# umodular_mega_shield_rev02.net
KiCad netlist of a schematic drawn in EAGLE
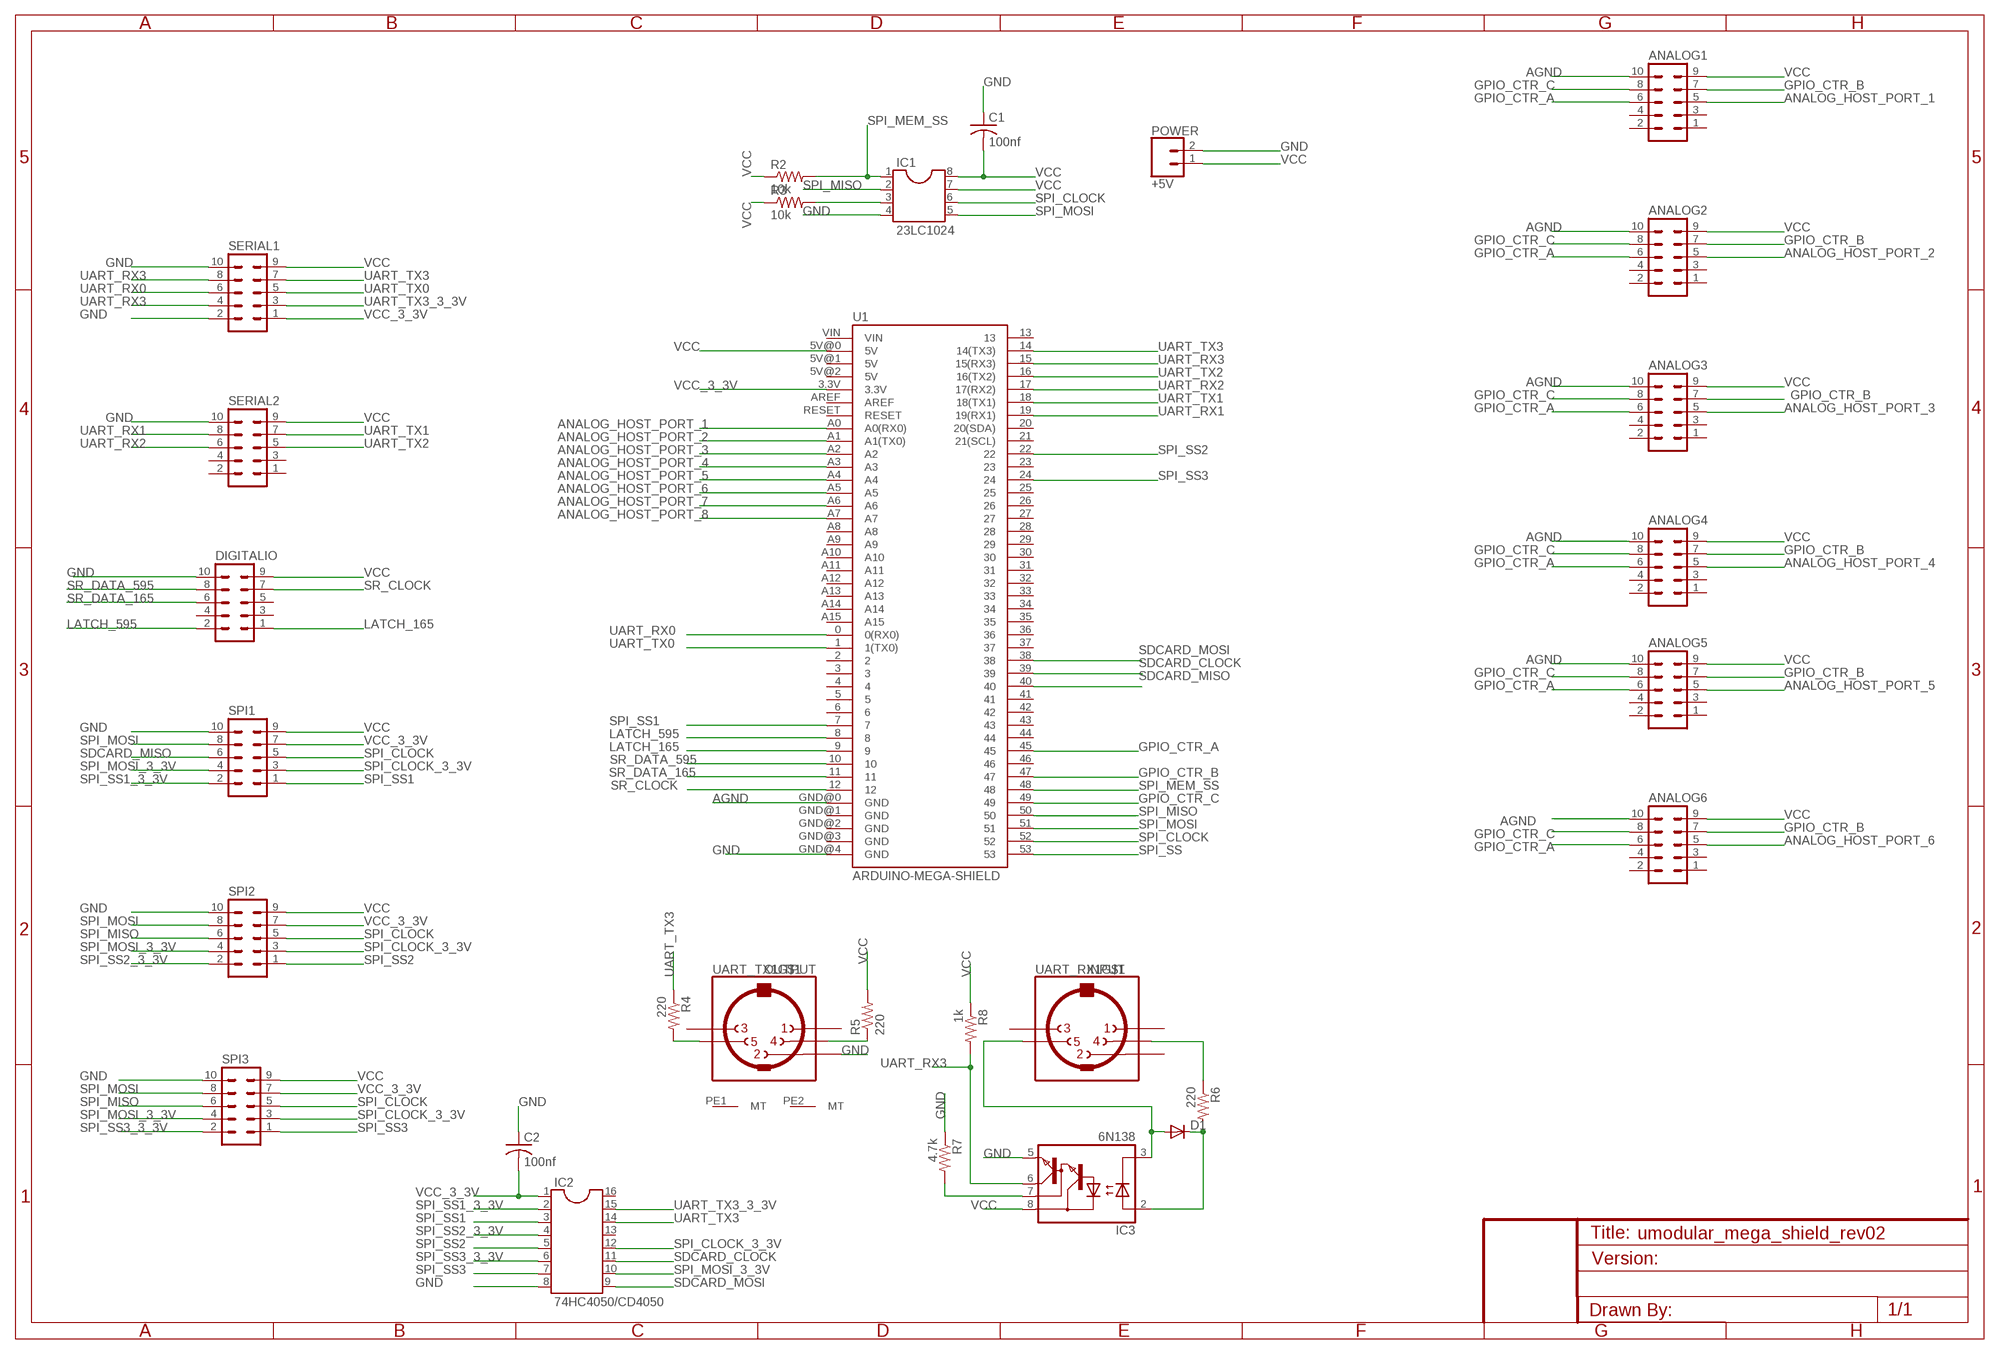
[diagram p0: schematic, sheet 1]

(export (version "E")
  (design (tool "Eeschema 10.0.6"))
  (components
    (comp (ref "ANALOG1")
      (value "MA05-2")
      (footprint "eagle-import:MA05-2")
      (libsource (lib "eagle-import") (part "MA05-2"))
    )
    (comp (ref "ANALOG2")
      (value "MA05-2")
      (footprint "eagle-import:MA05-2")
      (libsource (lib "eagle-import") (part "MA05-2"))
    )
    (comp (ref "ANALOG3")
      (value "MA05-2")
      (footprint "eagle-import:MA05-2")
      (libsource (lib "eagle-import") (part "MA05-2"))
    )
    (comp (ref "ANALOG4")
      (value "MA05-2")
      (footprint "eagle-import:MA05-2")
      (libsource (lib "eagle-import") (part "MA05-2"))
    )
    (comp (ref "ANALOG5")
      (value "MA05-2")
      (footprint "eagle-import:MA05-2")
      (libsource (lib "eagle-import") (part "MA05-2"))
    )
    (comp (ref "ANALOG6")
      (value "MA05-2")
      (footprint "eagle-import:MA05-2")
      (libsource (lib "eagle-import") (part "MA05-2"))
    )
    (comp (ref "C1")
      (value "100nf")
      (footprint "eagle-import:C050-024X044")
      (libsource (lib "eagle-import") (part "C-US050-024X044"))
    )
    (comp (ref "C2")
      (value "100nf")
      (footprint "eagle-import:C050-024X044")
      (libsource (lib "eagle-import") (part "C-US050-024X044"))
    )
    (comp (ref "D1")
      (value "1N4148DO35-7")
      (footprint "eagle-import:DO35-7")
      (libsource (lib "eagle-import") (part "1N4148DO35-7"))
    )
    (comp (ref "DIGITALIO")
      (value "MA05-2")
      (footprint "eagle-import:MA05-2")
      (libsource (lib "eagle-import") (part "MA05-2"))
    )
    (comp (ref "IC1")
      (value "23LC1024")
      (footprint "eagle-import:DIL08")
      (libsource (lib "eagle-import") (part "DIL8"))
    )
    (comp (ref "IC2")
      (value "74HC4050/CD4050")
      (footprint "eagle-import:DIL16")
      (libsource (lib "eagle-import") (part "DIL16"))
    )
    (comp (ref "IC3")
      (value "6N138")
      (footprint "eagle-import:DIL08")
      (fields (field (name "MF") "VISHAY/TELEFUNKEN"))
      (libsource (lib "eagle-import") (part "6N138"))
    )
    (comp (ref "POWER")
      (value "+5V")
      (footprint "eagle-import:1X02_LOCK_LONGPADS")
      (libsource (lib "eagle-import") (part "CONN_02LOCK_LONGPADS"))
    )
    (comp (ref "R2")
      (value "10k")
      (footprint "eagle-import:0204_7@1")
      (libsource (lib "eagle-import") (part "R-US_0204/7"))
    )
    (comp (ref "R3")
      (value "10k")
      (footprint "eagle-import:0204_7@1")
      (libsource (lib "eagle-import") (part "R-US_0204/7"))
    )
    (comp (ref "R4")
      (value "220")
      (footprint "eagle-import:0204_7@1")
      (libsource (lib "eagle-import") (part "R-US_0204/7"))
    )
    (comp (ref "R5")
      (value "220")
      (footprint "eagle-import:0204_7@1")
      (libsource (lib "eagle-import") (part "R-US_0204/7"))
    )
    (comp (ref "R6")
      (value "220")
      (footprint "eagle-import:0204_7@1")
      (libsource (lib "eagle-import") (part "R-US_0204/7"))
    )
    (comp (ref "R7")
      (value "4.7k")
      (footprint "eagle-import:0204_7@1")
      (libsource (lib "eagle-import") (part "R-US_0204/7"))
    )
    (comp (ref "R8")
      (value "1k")
      (footprint "eagle-import:0204_7@1")
      (libsource (lib "eagle-import") (part "R-US_0204/7"))
    )
    (comp (ref "SERIAL1")
      (value "MA05-2")
      (footprint "eagle-import:MA05-2")
      (libsource (lib "eagle-import") (part "MA05-2"))
    )
    (comp (ref "SERIAL2")
      (value "MA05-2")
      (footprint "eagle-import:MA05-2")
      (libsource (lib "eagle-import") (part "MA05-2"))
    )
    (comp (ref "SPI1")
      (value "MA05-2")
      (footprint "eagle-import:MA05-2")
      (libsource (lib "eagle-import") (part "MA05-2"))
    )
    (comp (ref "SPI2")
      (value "MA05-2")
      (footprint "eagle-import:MA05-2")
      (libsource (lib "eagle-import") (part "MA05-2"))
    )
    (comp (ref "SPI3")
      (value "MA05-2")
      (footprint "eagle-import:MA05-2")
      (libsource (lib "eagle-import") (part "MA05-2"))
    )
    (comp (ref "U1")
      (value "ARDUINO-MEGA-SHIELD")
      (footprint "eagle-import:ARDUINO_MEGA@1")
      (libsource (lib "eagle-import") (part "ARDUINO-MEGAFULL"))
    )
    (comp (ref "UART_RX1")
      (value "INPUT")
      (footprint "eagle-import:CP-2350")
      (libsource (lib "eagle-import") (part "MIDIJACK"))
    )
    (comp (ref "UART_TX1")
      (value "OUTPUT")
      (footprint "eagle-import:CP-2350")
      (libsource (lib "eagle-import") (part "MIDIJACK"))
    )
  )
  (nets
    (net (code "1") (name "/AGND") (class "Default")
      (node (ref "ANALOG1") (pin "10") (pinfunction "10_10") (pintype "passive"))
      (node (ref "ANALOG2") (pin "10") (pinfunction "10_10") (pintype "passive"))
      (node (ref "ANALOG3") (pin "10") (pinfunction "10_10") (pintype "passive"))
      (node (ref "ANALOG4") (pin "10") (pinfunction "10_10") (pintype "passive"))
      (node (ref "ANALOG5") (pin "10") (pinfunction "10_10") (pintype "passive"))
      (node (ref "ANALOG6") (pin "10") (pinfunction "10_10") (pintype "passive"))
      (node (ref "U1") (pin "GND@0") (pinfunction "GND_GND@0") (pintype "bidirectional"))
    )
    (net (code "2") (name "/ANALOG_HOST_PORT_1") (class "Default")
      (node (ref "ANALOG1") (pin "5") (pinfunction "5_5") (pintype "passive"))
      (node (ref "U1") (pin "A0") (pinfunction "A0(RX0)_A0") (pintype "bidirectional"))
    )
    (net (code "3") (name "/ANALOG_HOST_PORT_2") (class "Default")
      (node (ref "ANALOG2") (pin "5") (pinfunction "5_5") (pintype "passive"))
      (node (ref "U1") (pin "A1") (pinfunction "A1(TX0)_A1") (pintype "bidirectional"))
    )
    (net (code "4") (name "/ANALOG_HOST_PORT_3") (class "Default")
      (node (ref "ANALOG3") (pin "5") (pinfunction "5_5") (pintype "passive"))
      (node (ref "U1") (pin "A2") (pinfunction "A2_A2") (pintype "bidirectional"))
    )
    (net (code "5") (name "/ANALOG_HOST_PORT_4") (class "Default")
      (node (ref "ANALOG4") (pin "5") (pinfunction "5_5") (pintype "passive"))
      (node (ref "U1") (pin "A3") (pinfunction "A3_A3") (pintype "bidirectional"))
    )
    (net (code "6") (name "/ANALOG_HOST_PORT_5") (class "Default")
      (node (ref "ANALOG5") (pin "5") (pinfunction "5_5") (pintype "passive"))
      (node (ref "U1") (pin "A4") (pinfunction "A4_A4") (pintype "bidirectional"))
    )
    (net (code "7") (name "/ANALOG_HOST_PORT_6") (class "Default")
      (node (ref "ANALOG6") (pin "5") (pinfunction "5_5") (pintype "passive"))
      (node (ref "U1") (pin "A5") (pinfunction "A5_A5") (pintype "bidirectional"))
    )
    (net (code "8") (name "/ANALOG_HOST_PORT_7") (class "Default")
      (node (ref "U1") (pin "A6") (pinfunction "A6_A6") (pintype "bidirectional"))
    )
    (net (code "9") (name "/ANALOG_HOST_PORT_8") (class "Default")
      (node (ref "U1") (pin "A7") (pinfunction "A7_A7") (pintype "bidirectional"))
    )
    (net (code "10") (name "/GND") (class "Default")
      (node (ref "C1") (pin "1") (pinfunction "1_1") (pintype "passive"))
      (node (ref "C2") (pin "1") (pinfunction "1_1") (pintype "passive"))
      (node (ref "DIGITALIO") (pin "10") (pinfunction "10_10") (pintype "passive"))
      (node (ref "IC1") (pin "4") (pinfunction "4_4") (pintype "passive"))
      (node (ref "IC2") (pin "8") (pinfunction "8_8") (pintype "passive"))
      (node (ref "IC3") (pin "5") (pinfunction "GND_5") (pintype "passive"))
      (node (ref "POWER") (pin "2") (pinfunction "2_2") (pintype "passive"))
      (node (ref "R7") (pin "1") (pinfunction "1_1") (pintype "passive"))
      (node (ref "SERIAL1") (pin "10") (pinfunction "10_10") (pintype "passive"))
      (node (ref "SERIAL1") (pin "2") (pinfunction "2_2") (pintype "passive"))
      (node (ref "SERIAL2") (pin "10") (pinfunction "10_10") (pintype "passive"))
      (node (ref "SPI1") (pin "10") (pinfunction "10_10") (pintype "passive"))
      (node (ref "SPI2") (pin "10") (pinfunction "10_10") (pintype "passive"))
      (node (ref "SPI3") (pin "10") (pinfunction "10_10") (pintype "passive"))
      (node (ref "U1") (pin "GND@4") (pinfunction "GND_GND@4") (pintype "bidirectional"))
      (node (ref "UART_TX1") (pin "2") (pinfunction "2_2") (pintype "passive"))
    )
    (net (code "11") (name "/GPIO_CTR_A") (class "Default")
      (node (ref "ANALOG1") (pin "6") (pinfunction "6_6") (pintype "passive"))
      (node (ref "ANALOG2") (pin "6") (pinfunction "6_6") (pintype "passive"))
      (node (ref "ANALOG3") (pin "6") (pinfunction "6_6") (pintype "passive"))
      (node (ref "ANALOG4") (pin "6") (pinfunction "6_6") (pintype "passive"))
      (node (ref "ANALOG5") (pin "6") (pinfunction "6_6") (pintype "passive"))
      (node (ref "ANALOG6") (pin "6") (pinfunction "6_6") (pintype "passive"))
      (node (ref "U1") (pin "45") (pinfunction "45_45") (pintype "bidirectional"))
    )
    (net (code "12") (name "/GPIO_CTR_B") (class "Default")
      (node (ref "ANALOG1") (pin "7") (pinfunction "7_7") (pintype "passive"))
      (node (ref "ANALOG2") (pin "7") (pinfunction "7_7") (pintype "passive"))
      (node (ref "ANALOG3") (pin "7") (pinfunction "7_7") (pintype "passive"))
      (node (ref "ANALOG4") (pin "7") (pinfunction "7_7") (pintype "passive"))
      (node (ref "ANALOG5") (pin "7") (pinfunction "7_7") (pintype "passive"))
      (node (ref "ANALOG6") (pin "7") (pinfunction "7_7") (pintype "passive"))
      (node (ref "U1") (pin "47") (pinfunction "47_47") (pintype "bidirectional"))
    )
    (net (code "13") (name "/GPIO_CTR_C") (class "Default")
      (node (ref "ANALOG1") (pin "8") (pinfunction "8_8") (pintype "passive"))
      (node (ref "ANALOG2") (pin "8") (pinfunction "8_8") (pintype "passive"))
      (node (ref "ANALOG3") (pin "8") (pinfunction "8_8") (pintype "passive"))
      (node (ref "ANALOG4") (pin "8") (pinfunction "8_8") (pintype "passive"))
      (node (ref "ANALOG5") (pin "8") (pinfunction "8_8") (pintype "passive"))
      (node (ref "ANALOG6") (pin "8") (pinfunction "8_8") (pintype "passive"))
      (node (ref "U1") (pin "49") (pinfunction "49_49") (pintype "bidirectional"))
    )
    (net (code "14") (name "/LATCH_165") (class "Default")
      (node (ref "DIGITALIO") (pin "1") (pinfunction "1_1") (pintype "passive"))
      (node (ref "U1") (pin "9") (pinfunction "9_9") (pintype "bidirectional"))
    )
    (net (code "15") (name "/LATCH_595") (class "Default")
      (node (ref "DIGITALIO") (pin "2") (pinfunction "2_2") (pintype "passive"))
      (node (ref "U1") (pin "8") (pinfunction "8_8") (pintype "bidirectional"))
    )
    (net (code "16") (name "/SDCARD_CLOCK") (class "Default")
      (node (ref "IC2") (pin "11") (pinfunction "11_11") (pintype "passive"))
      (node (ref "U1") (pin "39") (pinfunction "39_39") (pintype "bidirectional"))
    )
    (net (code "17") (name "/SDCARD_MISO") (class "Default")
      (node (ref "SPI1") (pin "6") (pinfunction "6_6") (pintype "passive"))
      (node (ref "U1") (pin "40") (pinfunction "40_40") (pintype "bidirectional"))
    )
    (net (code "18") (name "/SDCARD_MOSI") (class "Default")
      (node (ref "IC2") (pin "9") (pinfunction "9_9") (pintype "passive"))
      (node (ref "U1") (pin "38") (pinfunction "38_38") (pintype "bidirectional"))
    )
    (net (code "19") (name "/SPI_CLOCK") (class "Default")
      (node (ref "IC1") (pin "6") (pinfunction "6_6") (pintype "passive"))
      (node (ref "SPI1") (pin "5") (pinfunction "5_5") (pintype "passive"))
      (node (ref "SPI2") (pin "5") (pinfunction "5_5") (pintype "passive"))
      (node (ref "SPI3") (pin "5") (pinfunction "5_5") (pintype "passive"))
      (node (ref "U1") (pin "52") (pinfunction "52_52") (pintype "bidirectional"))
    )
    (net (code "20") (name "/SPI_CLOCK_3_3V") (class "Default")
      (node (ref "IC2") (pin "12") (pinfunction "12_12") (pintype "passive"))
      (node (ref "SPI1") (pin "3") (pinfunction "3_3") (pintype "passive"))
      (node (ref "SPI2") (pin "3") (pinfunction "3_3") (pintype "passive"))
      (node (ref "SPI3") (pin "3") (pinfunction "3_3") (pintype "passive"))
    )
    (net (code "21") (name "/SPI_MEM_SS") (class "Default")
      (node (ref "IC1") (pin "1") (pinfunction "1_1") (pintype "passive"))
      (node (ref "R2") (pin "2") (pinfunction "2_2") (pintype "passive"))
      (node (ref "U1") (pin "48") (pinfunction "48_48") (pintype "bidirectional"))
    )
    (net (code "22") (name "/SPI_MISO") (class "Default")
      (node (ref "IC1") (pin "2") (pinfunction "2_2") (pintype "passive"))
      (node (ref "SPI2") (pin "6") (pinfunction "6_6") (pintype "passive"))
      (node (ref "SPI3") (pin "6") (pinfunction "6_6") (pintype "passive"))
      (node (ref "U1") (pin "50") (pinfunction "50_50") (pintype "bidirectional"))
    )
    (net (code "23") (name "/SPI_MOSI") (class "Default")
      (node (ref "IC1") (pin "5") (pinfunction "5_5") (pintype "passive"))
      (node (ref "SPI1") (pin "8") (pinfunction "8_8") (pintype "passive"))
      (node (ref "SPI2") (pin "8") (pinfunction "8_8") (pintype "passive"))
      (node (ref "SPI3") (pin "8") (pinfunction "8_8") (pintype "passive"))
      (node (ref "U1") (pin "51") (pinfunction "51_51") (pintype "bidirectional"))
    )
    (net (code "24") (name "/SPI_MOSI_3_3V") (class "Default")
      (node (ref "IC2") (pin "10") (pinfunction "10_10") (pintype "passive"))
      (node (ref "SPI1") (pin "4") (pinfunction "4_4") (pintype "passive"))
      (node (ref "SPI2") (pin "4") (pinfunction "4_4") (pintype "passive"))
      (node (ref "SPI3") (pin "4") (pinfunction "4_4") (pintype "passive"))
    )
    (net (code "25") (name "/SPI_SS") (class "Default")
      (node (ref "U1") (pin "53") (pinfunction "53_53") (pintype "bidirectional"))
    )
    (net (code "26") (name "/SPI_SS1") (class "Default")
      (node (ref "IC2") (pin "3") (pinfunction "3_3") (pintype "passive"))
      (node (ref "SPI1") (pin "1") (pinfunction "1_1") (pintype "passive"))
      (node (ref "U1") (pin "7") (pinfunction "7_7") (pintype "bidirectional"))
    )
    (net (code "27") (name "/SPI_SS1_3_3V") (class "Default")
      (node (ref "IC2") (pin "2") (pinfunction "2_2") (pintype "passive"))
      (node (ref "SPI1") (pin "2") (pinfunction "2_2") (pintype "passive"))
    )
    (net (code "28") (name "/SPI_SS2") (class "Default")
      (node (ref "IC2") (pin "5") (pinfunction "5_5") (pintype "passive"))
      (node (ref "SPI2") (pin "1") (pinfunction "1_1") (pintype "passive"))
      (node (ref "U1") (pin "22") (pinfunction "22_22") (pintype "bidirectional"))
    )
    (net (code "29") (name "/SPI_SS2_3_3V") (class "Default")
      (node (ref "IC2") (pin "4") (pinfunction "4_4") (pintype "passive"))
      (node (ref "SPI2") (pin "2") (pinfunction "2_2") (pintype "passive"))
    )
    (net (code "30") (name "/SPI_SS3") (class "Default")
      (node (ref "IC2") (pin "7") (pinfunction "7_7") (pintype "passive"))
      (node (ref "SPI3") (pin "1") (pinfunction "1_1") (pintype "passive"))
      (node (ref "U1") (pin "24") (pinfunction "24_24") (pintype "bidirectional"))
    )
    (net (code "31") (name "/SPI_SS3_3_3V") (class "Default")
      (node (ref "IC2") (pin "6") (pinfunction "6_6") (pintype "passive"))
      (node (ref "SPI3") (pin "2") (pinfunction "2_2") (pintype "passive"))
    )
    (net (code "32") (name "/SR_CLOCK") (class "Default")
      (node (ref "DIGITALIO") (pin "7") (pinfunction "7_7") (pintype "passive"))
      (node (ref "U1") (pin "12") (pinfunction "12_12") (pintype "bidirectional"))
    )
    (net (code "33") (name "/SR_DATA_165") (class "Default")
      (node (ref "DIGITALIO") (pin "6") (pinfunction "6_6") (pintype "passive"))
      (node (ref "U1") (pin "11") (pinfunction "11_11") (pintype "bidirectional"))
    )
    (net (code "34") (name "/SR_DATA_595") (class "Default")
      (node (ref "DIGITALIO") (pin "8") (pinfunction "8_8") (pintype "passive"))
      (node (ref "U1") (pin "10") (pinfunction "10_10") (pintype "bidirectional"))
    )
    (net (code "35") (name "/UART_RX0") (class "Default")
      (node (ref "SERIAL1") (pin "6") (pinfunction "6_6") (pintype "passive"))
      (node (ref "U1") (pin "0") (pinfunction "0(RX0)_0") (pintype "bidirectional"))
    )
    (net (code "36") (name "/UART_RX1") (class "Default")
      (node (ref "SERIAL2") (pin "8") (pinfunction "8_8") (pintype "passive"))
      (node (ref "U1") (pin "19") (pinfunction "19(RX1)_19") (pintype "bidirectional"))
    )
    (net (code "37") (name "/UART_RX2") (class "Default")
      (node (ref "SERIAL2") (pin "6") (pinfunction "6_6") (pintype "passive"))
      (node (ref "U1") (pin "17") (pinfunction "17(RX2)_17") (pintype "bidirectional"))
    )
    (net (code "38") (name "/UART_RX3") (class "Default")
      (node (ref "IC3") (pin "6") (pinfunction "VO_6") (pintype "passive"))
      (node (ref "R8") (pin "2") (pinfunction "2_2") (pintype "passive"))
      (node (ref "SERIAL1") (pin "4") (pinfunction "4_4") (pintype "passive"))
      (node (ref "SERIAL1") (pin "8") (pinfunction "8_8") (pintype "passive"))
      (node (ref "U1") (pin "15") (pinfunction "15(RX3)_15") (pintype "bidirectional"))
    )
    (net (code "39") (name "/UART_TX0") (class "Default")
      (node (ref "SERIAL1") (pin "5") (pinfunction "5_5") (pintype "passive"))
      (node (ref "U1") (pin "1") (pinfunction "1(TX0)_1") (pintype "bidirectional"))
    )
    (net (code "40") (name "/UART_TX1") (class "Default")
      (node (ref "SERIAL2") (pin "7") (pinfunction "7_7") (pintype "passive"))
      (node (ref "U1") (pin "18") (pinfunction "18(TX1)_18") (pintype "bidirectional"))
    )
    (net (code "41") (name "/UART_TX2") (class "Default")
      (node (ref "SERIAL2") (pin "5") (pinfunction "5_5") (pintype "passive"))
      (node (ref "U1") (pin "16") (pinfunction "16(TX2)_16") (pintype "bidirectional"))
    )
    (net (code "42") (name "/UART_TX3") (class "Default")
      (node (ref "IC2") (pin "14") (pinfunction "14_14") (pintype "passive"))
      (node (ref "R4") (pin "1") (pinfunction "1_1") (pintype "passive"))
      (node (ref "SERIAL1") (pin "7") (pinfunction "7_7") (pintype "passive"))
      (node (ref "U1") (pin "14") (pinfunction "14(TX3)_14") (pintype "bidirectional"))
    )
    (net (code "43") (name "/UART_TX3_3_3V") (class "Default")
      (node (ref "IC2") (pin "15") (pinfunction "15_15") (pintype "passive"))
      (node (ref "SERIAL1") (pin "3") (pinfunction "3_3") (pintype "passive"))
    )
    (net (code "44") (name "/VCC") (class "Default")
      (node (ref "ANALOG1") (pin "9") (pinfunction "9_9") (pintype "passive"))
      (node (ref "ANALOG2") (pin "9") (pinfunction "9_9") (pintype "passive"))
      (node (ref "ANALOG3") (pin "9") (pinfunction "9_9") (pintype "passive"))
      (node (ref "ANALOG4") (pin "9") (pinfunction "9_9") (pintype "passive"))
      (node (ref "ANALOG5") (pin "9") (pinfunction "9_9") (pintype "passive"))
      (node (ref "ANALOG6") (pin "9") (pinfunction "9_9") (pintype "passive"))
      (node (ref "C1") (pin "2") (pinfunction "2_2") (pintype "passive"))
      (node (ref "DIGITALIO") (pin "9") (pinfunction "9_9") (pintype "passive"))
      (node (ref "IC1") (pin "7") (pinfunction "7_7") (pintype "passive"))
      (node (ref "IC1") (pin "8") (pinfunction "8_8") (pintype "passive"))
      (node (ref "IC3") (pin "8") (pinfunction "VCC_8") (pintype "passive"))
      (node (ref "POWER") (pin "1") (pinfunction "1_1") (pintype "passive"))
      (node (ref "R2") (pin "1") (pinfunction "1_1") (pintype "passive"))
      (node (ref "R3") (pin "1") (pinfunction "1_1") (pintype "passive"))
      (node (ref "R5") (pin "2") (pinfunction "2_2") (pintype "passive"))
      (node (ref "R8") (pin "1") (pinfunction "1_1") (pintype "passive"))
      (node (ref "SERIAL1") (pin "9") (pinfunction "9_9") (pintype "passive"))
      (node (ref "SERIAL2") (pin "9") (pinfunction "9_9") (pintype "passive"))
      (node (ref "SPI1") (pin "9") (pinfunction "9_9") (pintype "passive"))
      (node (ref "SPI2") (pin "9") (pinfunction "9_9") (pintype "passive"))
      (node (ref "SPI3") (pin "9") (pinfunction "9_9") (pintype "passive"))
      (node (ref "U1") (pin "5V@0") (pinfunction "5V_5V@0") (pintype "bidirectional"))
    )
    (net (code "45") (name "/VCC_3_3V") (class "Default")
      (node (ref "C2") (pin "2") (pinfunction "2_2") (pintype "passive"))
      (node (ref "IC2") (pin "1") (pinfunction "1_1") (pintype "passive"))
      (node (ref "SERIAL1") (pin "1") (pinfunction "1_1") (pintype "passive"))
      (node (ref "SPI1") (pin "7") (pinfunction "7_7") (pintype "passive"))
      (node (ref "SPI2") (pin "7") (pinfunction "7_7") (pintype "passive"))
      (node (ref "SPI3") (pin "7") (pinfunction "7_7") (pintype "passive"))
      (node (ref "U1") (pin "3.3V") (pinfunction "3.3V_3.3V") (pintype "bidirectional"))
    )
    (net (code "46") (name "Net-(IC1-Pad3)") (class "Default")
      (node (ref "IC1") (pin "3") (pinfunction "3_3") (pintype "passive"))
      (node (ref "R3") (pin "2") (pinfunction "2_2") (pintype "passive"))
    )
    (net (code "47") (name "Net-(IC3-A)") (class "Default")
      (node (ref "D1") (pin "C") (pinfunction "C_C") (pintype "passive"))
      (node (ref "IC3") (pin "2") (pinfunction "A_2") (pintype "passive"))
      (node (ref "R6") (pin "2") (pinfunction "2_2") (pintype "passive"))
    )
    (net (code "48") (name "Net-(IC3-C)") (class "Default")
      (node (ref "D1") (pin "A") (pinfunction "A_A") (pintype "passive"))
      (node (ref "IC3") (pin "3") (pinfunction "C_3") (pintype "passive"))
      (node (ref "UART_RX1") (pin "5") (pinfunction "5_5") (pintype "passive"))
    )
    (net (code "49") (name "Net-(IC3-VB)") (class "Default")
      (node (ref "IC3") (pin "7") (pinfunction "VB_7") (pintype "passive"))
      (node (ref "R7") (pin "2") (pinfunction "2_2") (pintype "passive"))
    )
    (net (code "50") (name "Net-(R4-Pad2)") (class "Default")
      (node (ref "R4") (pin "2") (pinfunction "2_2") (pintype "passive"))
      (node (ref "UART_TX1") (pin "5") (pinfunction "5_5") (pintype "passive"))
    )
    (net (code "51") (name "Net-(R5-Pad1)") (class "Default")
      (node (ref "R5") (pin "1") (pinfunction "1_1") (pintype "passive"))
      (node (ref "UART_TX1") (pin "4") (pinfunction "4_4") (pintype "passive"))
    )
    (net (code "52") (name "Net-(R6-Pad1)") (class "Default")
      (node (ref "R6") (pin "1") (pinfunction "1_1") (pintype "passive"))
      (node (ref "UART_RX1") (pin "4") (pinfunction "4_4") (pintype "passive"))
    )
    (net (code "53") (name "unconnected-(ANALOG1-Pad1)") (class "Default")
      (node (ref "ANALOG1") (pin "1") (pinfunction "1_1") (pintype "passive"))
    )
    (net (code "54") (name "unconnected-(ANALOG1-Pad2)") (class "Default")
      (node (ref "ANALOG1") (pin "2") (pinfunction "2_2") (pintype "passive"))
    )
    (net (code "55") (name "unconnected-(ANALOG1-Pad3)") (class "Default")
      (node (ref "ANALOG1") (pin "3") (pinfunction "3_3") (pintype "passive"))
    )
    (net (code "56") (name "unconnected-(ANALOG1-Pad4)") (class "Default")
      (node (ref "ANALOG1") (pin "4") (pinfunction "4_4") (pintype "passive"))
    )
    (net (code "57") (name "unconnected-(ANALOG2-Pad1)") (class "Default")
      (node (ref "ANALOG2") (pin "1") (pinfunction "1_1") (pintype "passive"))
    )
    (net (code "58") (name "unconnected-(ANALOG2-Pad2)") (class "Default")
      (node (ref "ANALOG2") (pin "2") (pinfunction "2_2") (pintype "passive"))
    )
    (net (code "59") (name "unconnected-(ANALOG2-Pad3)") (class "Default")
      (node (ref "ANALOG2") (pin "3") (pinfunction "3_3") (pintype "passive"))
    )
    (net (code "60") (name "unconnected-(ANALOG2-Pad4)") (class "Default")
      (node (ref "ANALOG2") (pin "4") (pinfunction "4_4") (pintype "passive"))
    )
    (net (code "61") (name "unconnected-(ANALOG3-Pad1)") (class "Default")
      (node (ref "ANALOG3") (pin "1") (pinfunction "1_1") (pintype "passive"))
    )
    (net (code "62") (name "unconnected-(ANALOG3-Pad2)") (class "Default")
      (node (ref "ANALOG3") (pin "2") (pinfunction "2_2") (pintype "passive"))
    )
    (net (code "63") (name "unconnected-(ANALOG3-Pad3)") (class "Default")
      (node (ref "ANALOG3") (pin "3") (pinfunction "3_3") (pintype "passive"))
    )
    (net (code "64") (name "unconnected-(ANALOG3-Pad4)") (class "Default")
      (node (ref "ANALOG3") (pin "4") (pinfunction "4_4") (pintype "passive"))
    )
    (net (code "65") (name "unconnected-(ANALOG4-Pad1)") (class "Default")
      (node (ref "ANALOG4") (pin "1") (pinfunction "1_1") (pintype "passive"))
    )
    (net (code "66") (name "unconnected-(ANALOG4-Pad2)") (class "Default")
      (node (ref "ANALOG4") (pin "2") (pinfunction "2_2") (pintype "passive"))
    )
    (net (code "67") (name "unconnected-(ANALOG4-Pad3)") (class "Default")
      (node (ref "ANALOG4") (pin "3") (pinfunction "3_3") (pintype "passive"))
    )
    (net (code "68") (name "unconnected-(ANALOG4-Pad4)") (class "Default")
      (node (ref "ANALOG4") (pin "4") (pinfunction "4_4") (pintype "passive"))
    )
    (net (code "69") (name "unconnected-(ANALOG5-Pad1)") (class "Default")
      (node (ref "ANALOG5") (pin "1") (pinfunction "1_1") (pintype "passive"))
    )
    (net (code "70") (name "unconnected-(ANALOG5-Pad2)") (class "Default")
      (node (ref "ANALOG5") (pin "2") (pinfunction "2_2") (pintype "passive"))
    )
    (net (code "71") (name "unconnected-(ANALOG5-Pad3)") (class "Default")
      (node (ref "ANALOG5") (pin "3") (pinfunction "3_3") (pintype "passive"))
    )
    (net (code "72") (name "unconnected-(ANALOG5-Pad4)") (class "Default")
      (node (ref "ANALOG5") (pin "4") (pinfunction "4_4") (pintype "passive"))
    )
    (net (code "73") (name "unconnected-(ANALOG6-Pad1)") (class "Default")
      (node (ref "ANALOG6") (pin "1") (pinfunction "1_1") (pintype "passive"))
    )
    (net (code "74") (name "unconnected-(ANALOG6-Pad2)") (class "Default")
      (node (ref "ANALOG6") (pin "2") (pinfunction "2_2") (pintype "passive"))
    )
    (net (code "75") (name "unconnected-(ANALOG6-Pad3)") (class "Default")
      (node (ref "ANALOG6") (pin "3") (pinfunction "3_3") (pintype "passive"))
    )
    (net (code "76") (name "unconnected-(ANALOG6-Pad4)") (class "Default")
      (node (ref "ANALOG6") (pin "4") (pinfunction "4_4") (pintype "passive"))
    )
    (net (code "77") (name "unconnected-(DIGITALIO-Pad3)") (class "Default")
      (node (ref "DIGITALIO") (pin "3") (pinfunction "3_3") (pintype "passive"))
    )
    (net (code "78") (name "unconnected-(DIGITALIO-Pad4)") (class "Default")
      (node (ref "DIGITALIO") (pin "4") (pinfunction "4_4") (pintype "passive"))
    )
    (net (code "79") (name "unconnected-(DIGITALIO-Pad5)") (class "Default")
      (node (ref "DIGITALIO") (pin "5") (pinfunction "5_5") (pintype "passive"))
    )
    (net (code "80") (name "unconnected-(IC2-Pad13)") (class "Default")
      (node (ref "IC2") (pin "13") (pinfunction "13_13") (pintype "passive"))
    )
    (net (code "81") (name "unconnected-(IC2-Pad16)") (class "Default")
      (node (ref "IC2") (pin "16") (pinfunction "16_16") (pintype "passive"))
    )
    (net (code "82") (name "unconnected-(SERIAL2-Pad1)") (class "Default")
      (node (ref "SERIAL2") (pin "1") (pinfunction "1_1") (pintype "passive"))
    )
    (net (code "83") (name "unconnected-(SERIAL2-Pad2)") (class "Default")
      (node (ref "SERIAL2") (pin "2") (pinfunction "2_2") (pintype "passive"))
    )
    (net (code "84") (name "unconnected-(SERIAL2-Pad3)") (class "Default")
      (node (ref "SERIAL2") (pin "3") (pinfunction "3_3") (pintype "passive"))
    )
    (net (code "85") (name "unconnected-(SERIAL2-Pad4)") (class "Default")
      (node (ref "SERIAL2") (pin "4") (pinfunction "4_4") (pintype "passive"))
    )
    (net (code "86") (name "unconnected-(U1-5V-Pad5V@1)") (class "Default")
      (node (ref "U1") (pin "5V@1") (pinfunction "5V_5V@1") (pintype "bidirectional"))
    )
    (net (code "87") (name "unconnected-(U1-5V-Pad5V@2)") (class "Default")
      (node (ref "U1") (pin "5V@2") (pinfunction "5V_5V@2") (pintype "bidirectional"))
    )
    (net (code "88") (name "unconnected-(U1-20(SDA)-Pad20)") (class "Default")
      (node (ref "U1") (pin "20") (pinfunction "20(SDA)_20") (pintype "bidirectional"))
    )
    (net (code "89") (name "unconnected-(U1-21(SCL)-Pad21)") (class "Default")
      (node (ref "U1") (pin "21") (pinfunction "21(SCL)_21") (pintype "bidirectional"))
    )
    (net (code "90") (name "unconnected-(U1-GND-PadGND@1)") (class "Default")
      (node (ref "U1") (pin "GND@1") (pinfunction "GND_GND@1") (pintype "bidirectional"))
    )
    (net (code "91") (name "unconnected-(U1-GND-PadGND@2)") (class "Default")
      (node (ref "U1") (pin "GND@2") (pinfunction "GND_GND@2") (pintype "bidirectional"))
    )
    (net (code "92") (name "unconnected-(U1-GND-PadGND@3)") (class "Default")
      (node (ref "U1") (pin "GND@3") (pinfunction "GND_GND@3") (pintype "bidirectional"))
    )
    (net (code "93") (name "unconnected-(U1-Pad2)") (class "Default")
      (node (ref "U1") (pin "2") (pinfunction "2_2") (pintype "bidirectional"))
    )
    (net (code "94") (name "unconnected-(U1-Pad3)") (class "Default")
      (node (ref "U1") (pin "3") (pinfunction "3_3") (pintype "bidirectional"))
    )
    (net (code "95") (name "unconnected-(U1-Pad4)") (class "Default")
      (node (ref "U1") (pin "4") (pinfunction "4_4") (pintype "bidirectional"))
    )
    (net (code "96") (name "unconnected-(U1-Pad5)") (class "Default")
      (node (ref "U1") (pin "5") (pinfunction "5_5") (pintype "bidirectional"))
    )
    (net (code "97") (name "unconnected-(U1-Pad6)") (class "Default")
      (node (ref "U1") (pin "6") (pinfunction "6_6") (pintype "bidirectional"))
    )
    (net (code "98") (name "unconnected-(U1-Pad13)") (class "Default")
      (node (ref "U1") (pin "13") (pinfunction "13_13") (pintype "bidirectional"))
    )
    (net (code "99") (name "unconnected-(U1-Pad23)") (class "Default")
      (node (ref "U1") (pin "23") (pinfunction "23_23") (pintype "bidirectional"))
    )
    (net (code "100") (name "unconnected-(U1-Pad25)") (class "Default")
      (node (ref "U1") (pin "25") (pinfunction "25_25") (pintype "bidirectional"))
    )
    (net (code "101") (name "unconnected-(U1-Pad26)") (class "Default")
      (node (ref "U1") (pin "26") (pinfunction "26_26") (pintype "bidirectional"))
    )
    (net (code "102") (name "unconnected-(U1-Pad27)") (class "Default")
      (node (ref "U1") (pin "27") (pinfunction "27_27") (pintype "bidirectional"))
    )
    (net (code "103") (name "unconnected-(U1-Pad28)") (class "Default")
      (node (ref "U1") (pin "28") (pinfunction "28_28") (pintype "bidirectional"))
    )
    (net (code "104") (name "unconnected-(U1-Pad29)") (class "Default")
      (node (ref "U1") (pin "29") (pinfunction "29_29") (pintype "bidirectional"))
    )
    (net (code "105") (name "unconnected-(U1-Pad30)") (class "Default")
      (node (ref "U1") (pin "30") (pinfunction "30_30") (pintype "bidirectional"))
    )
    (net (code "106") (name "unconnected-(U1-Pad31)") (class "Default")
      (node (ref "U1") (pin "31") (pinfunction "31_31") (pintype "bidirectional"))
    )
    (net (code "107") (name "unconnected-(U1-Pad32)") (class "Default")
      (node (ref "U1") (pin "32") (pinfunction "32_32") (pintype "bidirectional"))
    )
    (net (code "108") (name "unconnected-(U1-Pad33)") (class "Default")
      (node (ref "U1") (pin "33") (pinfunction "33_33") (pintype "bidirectional"))
    )
    (net (code "109") (name "unconnected-(U1-Pad34)") (class "Default")
      (node (ref "U1") (pin "34") (pinfunction "34_34") (pintype "bidirectional"))
    )
    (net (code "110") (name "unconnected-(U1-Pad35)") (class "Default")
      (node (ref "U1") (pin "35") (pinfunction "35_35") (pintype "bidirectional"))
    )
    (net (code "111") (name "unconnected-(U1-Pad36)") (class "Default")
      (node (ref "U1") (pin "36") (pinfunction "36_36") (pintype "bidirectional"))
    )
    (net (code "112") (name "unconnected-(U1-Pad37)") (class "Default")
      (node (ref "U1") (pin "37") (pinfunction "37_37") (pintype "bidirectional"))
    )
    (net (code "113") (name "unconnected-(U1-Pad41)") (class "Default")
      (node (ref "U1") (pin "41") (pinfunction "41_41") (pintype "bidirectional"))
    )
    (net (code "114") (name "unconnected-(U1-Pad42)") (class "Default")
      (node (ref "U1") (pin "42") (pinfunction "42_42") (pintype "bidirectional"))
    )
    (net (code "115") (name "unconnected-(U1-Pad43)") (class "Default")
      (node (ref "U1") (pin "43") (pinfunction "43_43") (pintype "bidirectional"))
    )
    (net (code "116") (name "unconnected-(U1-Pad44)") (class "Default")
      (node (ref "U1") (pin "44") (pinfunction "44_44") (pintype "bidirectional"))
    )
    (net (code "117") (name "unconnected-(U1-Pad46)") (class "Default")
      (node (ref "U1") (pin "46") (pinfunction "46_46") (pintype "bidirectional"))
    )
    (net (code "118") (name "unconnected-(U1-PadA8)") (class "Default")
      (node (ref "U1") (pin "A8") (pinfunction "A8_A8") (pintype "bidirectional"))
    )
    (net (code "119") (name "unconnected-(U1-PadA9)") (class "Default")
      (node (ref "U1") (pin "A9") (pinfunction "A9_A9") (pintype "bidirectional"))
    )
    (net (code "120") (name "unconnected-(U1-PadA10)") (class "Default")
      (node (ref "U1") (pin "A10") (pinfunction "A10_A10") (pintype "bidirectional"))
    )
    (net (code "121") (name "unconnected-(U1-PadA11)") (class "Default")
      (node (ref "U1") (pin "A11") (pinfunction "A11_A11") (pintype "bidirectional"))
    )
    (net (code "122") (name "unconnected-(U1-PadA12)") (class "Default")
      (node (ref "U1") (pin "A12") (pinfunction "A12_A12") (pintype "bidirectional"))
    )
    (net (code "123") (name "unconnected-(U1-PadA13)") (class "Default")
      (node (ref "U1") (pin "A13") (pinfunction "A13_A13") (pintype "bidirectional"))
    )
    (net (code "124") (name "unconnected-(U1-PadA14)") (class "Default")
      (node (ref "U1") (pin "A14") (pinfunction "A14_A14") (pintype "bidirectional"))
    )
    (net (code "125") (name "unconnected-(U1-PadA15)") (class "Default")
      (node (ref "U1") (pin "A15") (pinfunction "A15_A15") (pintype "bidirectional"))
    )
    (net (code "126") (name "unconnected-(U1-PadAREF)") (class "Default")
      (node (ref "U1") (pin "AREF") (pinfunction "AREF_AREF") (pintype "bidirectional"))
    )
    (net (code "127") (name "unconnected-(U1-PadRESET)") (class "Default")
      (node (ref "U1") (pin "RESET") (pinfunction "RESET_RESET") (pintype "bidirectional"))
    )
    (net (code "128") (name "unconnected-(U1-PadVIN)") (class "Default")
      (node (ref "U1") (pin "VIN") (pinfunction "VIN_VIN") (pintype "bidirectional"))
    )
    (net (code "129") (name "unconnected-(UART_RX1-Pad1)") (class "Default")
      (node (ref "UART_RX1") (pin "1") (pinfunction "1_1") (pintype "passive"))
    )
    (net (code "130") (name "unconnected-(UART_RX1-Pad2)") (class "Default")
      (node (ref "UART_RX1") (pin "2") (pinfunction "2_2") (pintype "passive"))
    )
    (net (code "131") (name "unconnected-(UART_RX1-Pad3)") (class "Default")
      (node (ref "UART_RX1") (pin "3") (pinfunction "3_3") (pintype "passive"))
    )
    (net (code "132") (name "unconnected-(UART_TX1-Pad1)") (class "Default")
      (node (ref "UART_TX1") (pin "1") (pinfunction "1_1") (pintype "passive"))
    )
    (net (code "133") (name "unconnected-(UART_TX1-Pad3)") (class "Default")
      (node (ref "UART_TX1") (pin "3") (pinfunction "3_3") (pintype "passive"))
    )
    (net (code "134") (name "unconnected-(UART_TX1D-MT-PadPE1)") (class "Default")
      (node (ref "UART_TX1") (pin "PE1") (pinfunction "MT_PE1") (pintype "passive"))
    )
    (net (code "135") (name "unconnected-(UART_TX1E-MT-PadPE2)") (class "Default")
      (node (ref "UART_TX1") (pin "PE2") (pinfunction "MT_PE2") (pintype "passive"))
    )
  )
)
